# EL-23_Main.net
KiCad netlist of a schematic drawn in Altium Designer
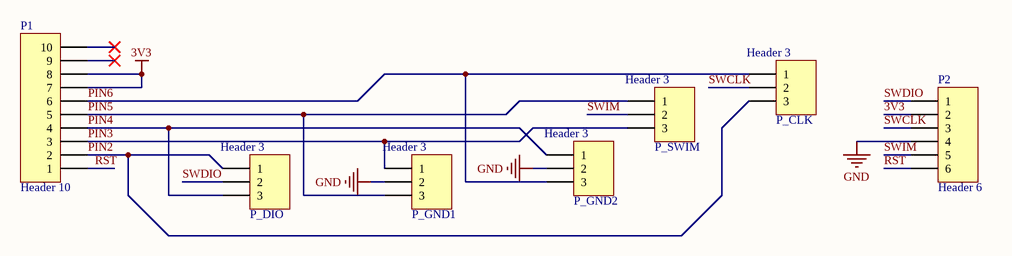
[diagram p0: EL-23 Main.SchDoc]

(export (version "E")
  (design (tool "Eeschema 10.0.6"))
  (components
    (comp (ref "P1")
      (value "Header 10")
      (footprint "SHDRV10W102P254_2X5_2032X895X915P")
      (description "Header, 10-Pin")
      (libsource (lib "agh_racing_2018") (part "Header 10"))
    )
    (comp (ref "P2")
      (value "Header 6")
      (footprint "HEADER_2x3_1_17_WOMAN_THT")
      (description "Header, 6-Pin")
      (libsource (lib "agh_racing_2018") (part "Header 6"))
    )
    (comp (ref "P_CLK")
      (value "Header 3")
      (footprint "HEADER 1x3 1.27mm")
      (description "Header, 3-Pin")
      (libsource (lib "agh_racing_2018") (part "Header 3"))
    )
    (comp (ref "P_DIO")
      (value "Header 3")
      (footprint "HEADER 1x3 1.27mm")
      (description "Header, 3-Pin")
      (libsource (lib "agh_racing_2018") (part "Header 3"))
    )
    (comp (ref "P_GND1")
      (value "Header 3")
      (footprint "HEADER 1x3 1.27mm")
      (description "Header, 3-Pin")
      (libsource (lib "agh_racing_2018") (part "Header 3"))
    )
    (comp (ref "P_GND2")
      (value "Header 3")
      (footprint "HEADER 1x3 1.27mm")
      (description "Header, 3-Pin")
      (libsource (lib "agh_racing_2018") (part "Header 3"))
    )
    (comp (ref "P_SWIM")
      (value "Header 3")
      (footprint "HEADER 1x3 1.27mm")
      (description "Header, 3-Pin")
      (libsource (lib "agh_racing_2018") (part "Header 3"))
    )
  )
  (nets
    (net (code "1") (name "/PIN2") (class "Default")
      (node (ref "P1") (pin "2") (pinfunction "2_2") (pintype "passive"))
      (node (ref "P_CLK") (pin "3") (pinfunction "3_3") (pintype "passive"))
      (node (ref "P_DIO") (pin "1") (pinfunction "1_1") (pintype "passive"))
    )
    (net (code "2") (name "/PIN3") (class "Default")
      (node (ref "P1") (pin "3") (pinfunction "3_3") (pintype "passive"))
      (node (ref "P_GND1") (pin "1") (pinfunction "1_1") (pintype "passive"))
      (node (ref "P_SWIM") (pin "3") (pinfunction "3_3") (pintype "passive"))
    )
    (net (code "3") (name "/PIN4") (class "Default")
      (node (ref "P1") (pin "4") (pinfunction "4_4") (pintype "passive"))
      (node (ref "P_DIO") (pin "3") (pinfunction "3_3") (pintype "passive"))
      (node (ref "P_GND2") (pin "1") (pinfunction "1_1") (pintype "passive"))
    )
    (net (code "4") (name "/PIN5") (class "Default")
      (node (ref "P1") (pin "5") (pinfunction "5_5") (pintype "passive"))
      (node (ref "P_GND1") (pin "3") (pinfunction "3_3") (pintype "passive"))
      (node (ref "P_SWIM") (pin "1") (pinfunction "1_1") (pintype "passive"))
    )
    (net (code "5") (name "/PIN6") (class "Default")
      (node (ref "P1") (pin "6") (pinfunction "6_6") (pintype "passive"))
      (node (ref "P_CLK") (pin "1") (pinfunction "1_1") (pintype "passive"))
      (node (ref "P_GND2") (pin "3") (pinfunction "3_3") (pintype "passive"))
    )
    (net (code "6") (name "/RST") (class "Default")
      (node (ref "P1") (pin "1") (pinfunction "1_1") (pintype "passive"))
      (node (ref "P2") (pin "6") (pinfunction "6_6") (pintype "passive"))
    )
    (net (code "7") (name "/SWCLK") (class "Default")
      (node (ref "P2") (pin "3") (pinfunction "3_3") (pintype "passive"))
      (node (ref "P_CLK") (pin "2") (pinfunction "2_2") (pintype "passive"))
    )
    (net (code "8") (name "/SWDIO") (class "Default")
      (node (ref "P2") (pin "1") (pinfunction "1_1") (pintype "passive"))
      (node (ref "P_DIO") (pin "2") (pinfunction "2_2") (pintype "passive"))
    )
    (net (code "9") (name "/SWIM") (class "Default")
      (node (ref "P2") (pin "5") (pinfunction "5_5") (pintype "passive"))
      (node (ref "P_SWIM") (pin "2") (pinfunction "2_2") (pintype "passive"))
    )
    (net (code "10") (name "3V3") (class "Default")
      (node (ref "P1") (pin "7") (pinfunction "7_7") (pintype "passive"))
      (node (ref "P1") (pin "8") (pinfunction "8_8") (pintype "passive"))
      (node (ref "P2") (pin "2") (pinfunction "2_2") (pintype "passive"))
    )
    (net (code "11") (name "GND") (class "Default")
      (node (ref "P2") (pin "4") (pinfunction "4_4") (pintype "passive"))
      (node (ref "P_GND1") (pin "2") (pinfunction "2_2") (pintype "passive"))
      (node (ref "P_GND2") (pin "2") (pinfunction "2_2") (pintype "passive"))
    )
    (net (code "12") (name "unconnected-(P1-Pad9)") (class "Default")
      (node (ref "P1") (pin "9") (pinfunction "9_9") (pintype "passive+no_connect"))
    )
    (net (code "13") (name "unconnected-(P1-Pad10)") (class "Default")
      (node (ref "P1") (pin "10") (pinfunction "10_10") (pintype "passive+no_connect"))
    )
  )
)
